# STM32F407_1.net
KiCad netlist of a schematic drawn in Altium Designer
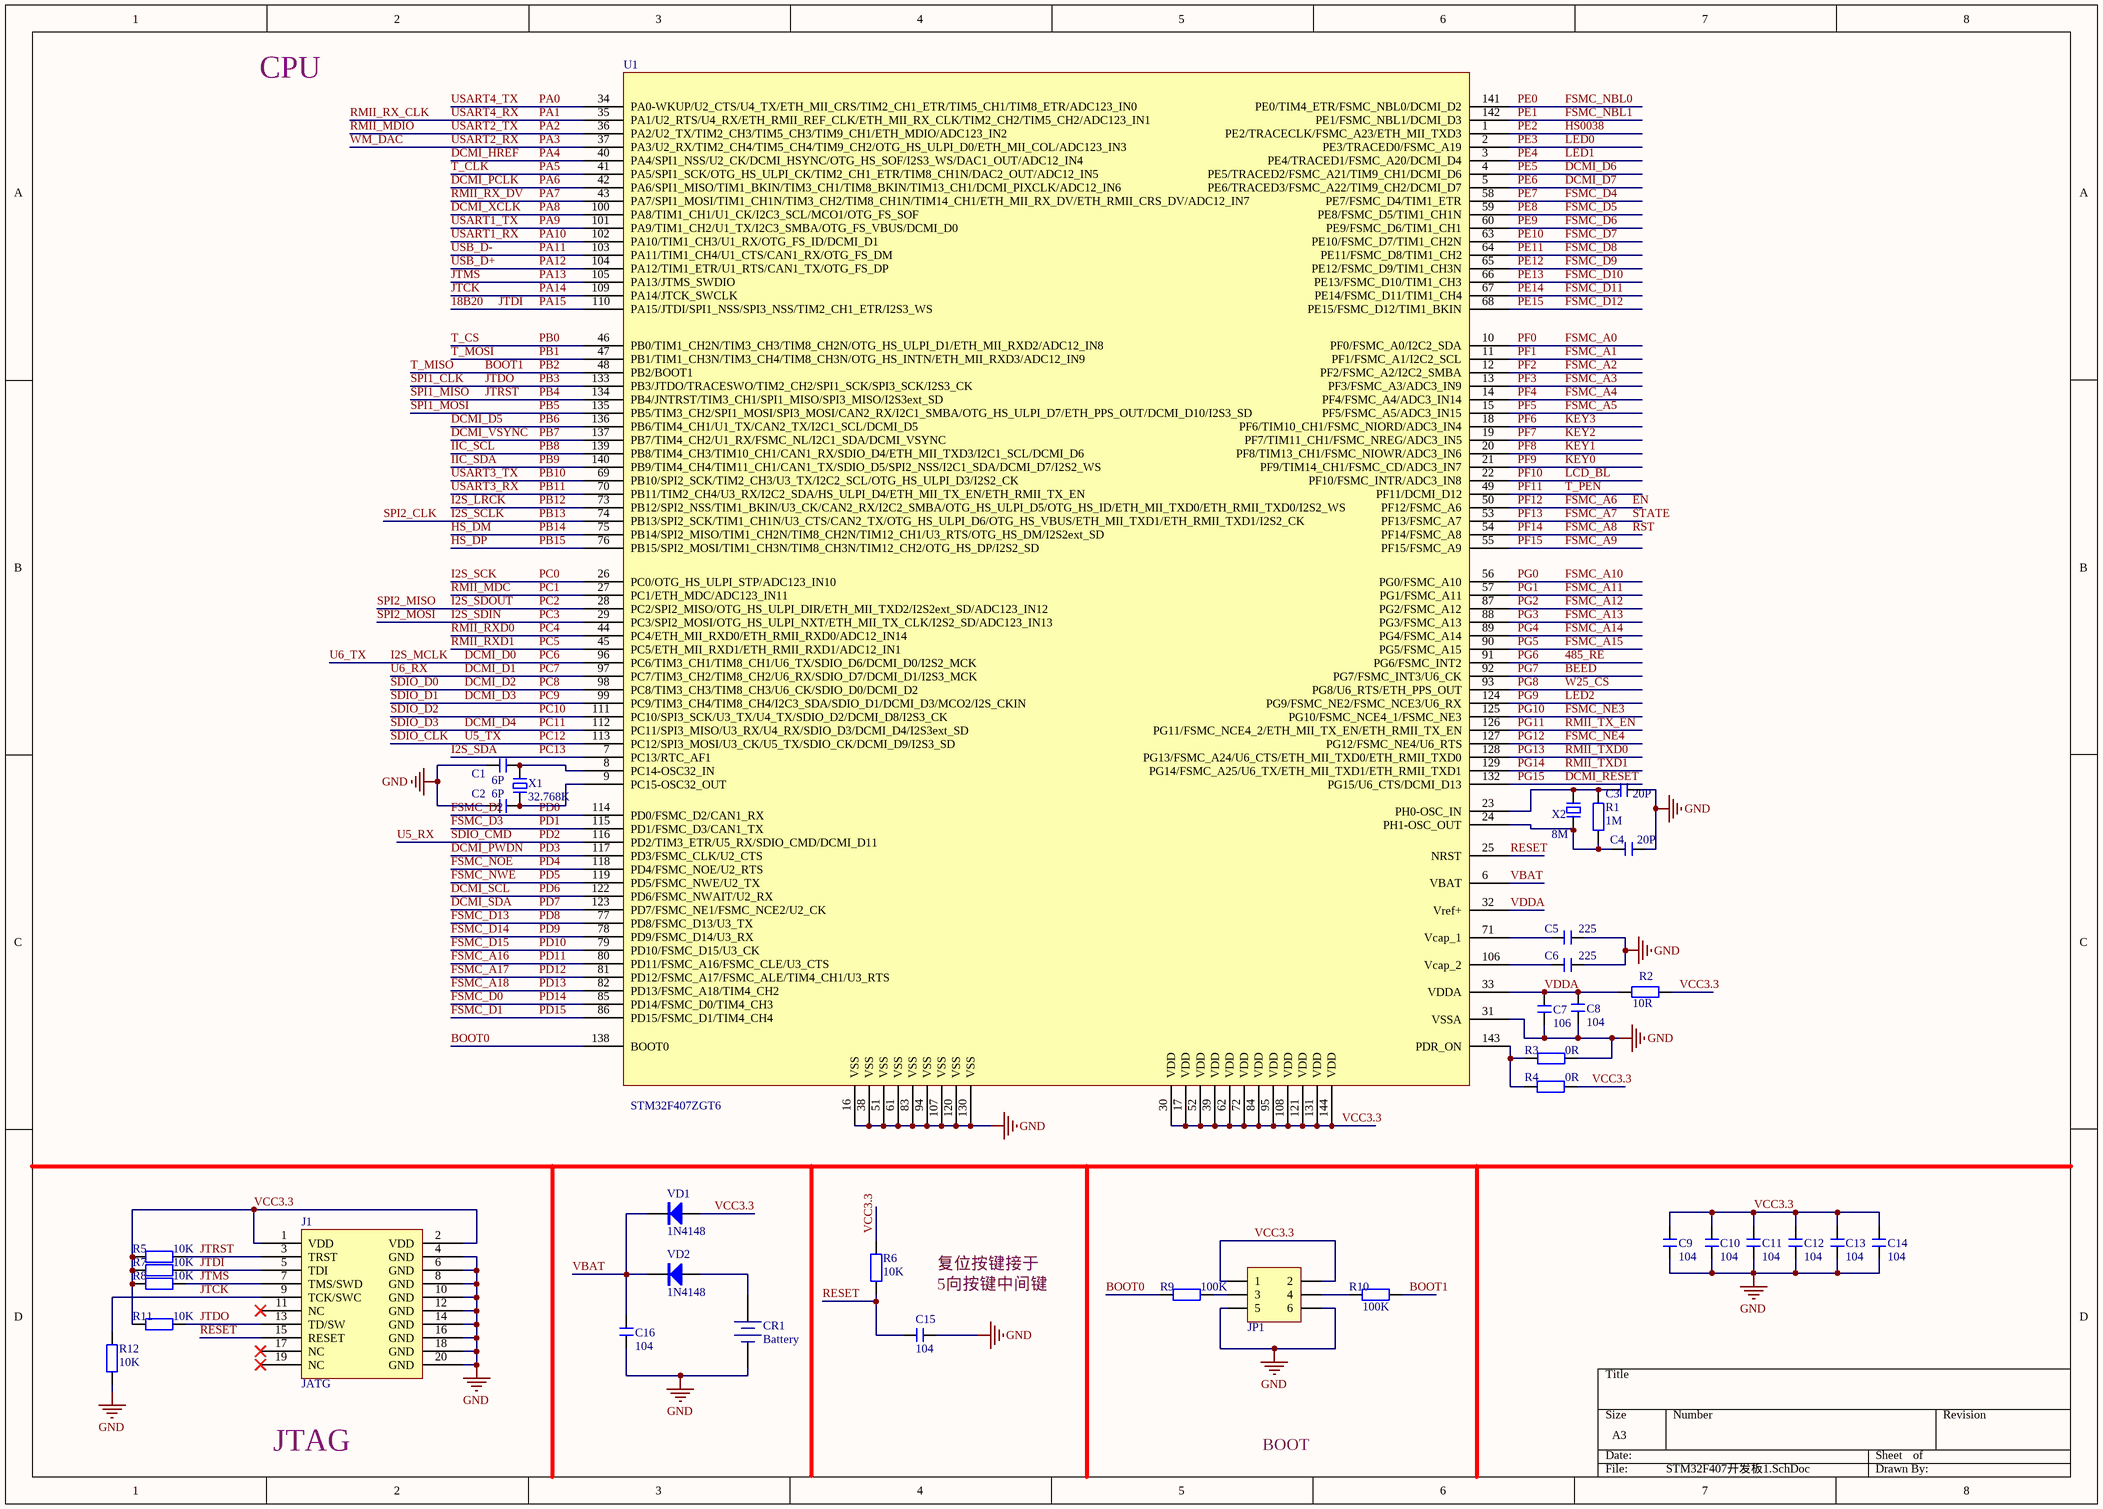
[diagram p0: STM32F407开发板1.SchDoc]

(export (version "E")
  (design (tool "Eeschema 10.0.6"))
  (components
    (comp (ref "C1")
      (value "6P")
      (footprint "C 0603")
      (description "无极性贴片电容")
      (fields (field (name "版权归属") "源创客"))
      (libsource (lib "电阻-电容-电感") (part "C"))
    )
    (comp (ref "C2")
      (value "6P")
      (footprint "C 0603")
      (description "无极性贴片电容")
      (fields (field (name "版权归属") "源创客"))
      (libsource (lib "电阻-电容-电感") (part "C"))
    )
    (comp (ref "C3")
      (value "20P")
      (footprint "C 0603")
      (description "无极性贴片电容")
      (fields (field (name "版权归属") "源创客"))
      (libsource (lib "电阻-电容-电感") (part "C"))
    )
    (comp (ref "C4")
      (value "20P")
      (footprint "C 0603")
      (description "无极性贴片电容")
      (fields (field (name "版权归属") "源创客"))
      (libsource (lib "电阻-电容-电感") (part "C"))
    )
    (comp (ref "C5")
      (value "225")
      (footprint "C 0603")
      (description "无极性贴片电容")
      (fields (field (name "版权归属") "源创客"))
      (libsource (lib "电阻-电容-电感") (part "C"))
    )
    (comp (ref "C6")
      (value "225")
      (footprint "C 0603")
      (description "无极性贴片电容")
      (fields (field (name "版权归属") "源创客"))
      (libsource (lib "电阻-电容-电感") (part "C"))
    )
    (comp (ref "C7")
      (value "106")
      (footprint "C 0603")
      (description "无极性贴片电容")
      (fields (field (name "版权归属") "源创客"))
      (libsource (lib "电阻-电容-电感") (part "C"))
    )
    (comp (ref "C8")
      (value "104")
      (footprint "C 0603")
      (description "无极性贴片电容")
      (fields (field (name "版权归属") "源创客"))
      (libsource (lib "电阻-电容-电感") (part "C"))
    )
    (comp (ref "C9")
      (value "104")
      (footprint "C 0603")
      (description "无极性贴片电容")
      (fields (field (name "版权归属") "源创客"))
      (libsource (lib "电阻-电容-电感") (part "C"))
    )
    (comp (ref "C10")
      (value "104")
      (footprint "C 0603")
      (description "无极性贴片电容")
      (fields (field (name "版权归属") "源创客"))
      (libsource (lib "电阻-电容-电感") (part "C"))
    )
    (comp (ref "C11")
      (value "104")
      (footprint "C 0603")
      (description "无极性贴片电容")
      (fields (field (name "版权归属") "源创客"))
      (libsource (lib "电阻-电容-电感") (part "C"))
    )
    (comp (ref "C12")
      (value "104")
      (footprint "C 0603")
      (description "无极性贴片电容")
      (fields (field (name "版权归属") "源创客"))
      (libsource (lib "电阻-电容-电感") (part "C"))
    )
    (comp (ref "C13")
      (value "104")
      (footprint "C 0603")
      (description "无极性贴片电容")
      (fields (field (name "版权归属") "源创客"))
      (libsource (lib "电阻-电容-电感") (part "C"))
    )
    (comp (ref "C14")
      (value "104")
      (footprint "C 0603")
      (description "无极性贴片电容")
      (fields (field (name "版权归属") "源创客"))
      (libsource (lib "电阻-电容-电感") (part "C"))
    )
    (comp (ref "C15")
      (value "104")
      (footprint "C 0603")
      (description "无极性贴片电容")
      (fields (field (name "版权归属") "源创客"))
      (libsource (lib "电阻-电容-电感") (part "C"))
    )
    (comp (ref "C16")
      (value "104")
      (footprint "C 0603")
      (description "无极性贴片电容")
      (fields (field (name "版权归属") "源创客"))
      (libsource (lib "电阻-电容-电感") (part "C"))
    )
    (comp (ref "CR1")
      (value "Battery")
      (footprint "CR1220_A")
      (description "微型电池")
      (fields (field (name "版权归属") "源创客"))
      (libsource (lib "未分类器件") (part "CR-3V"))
    )
    (comp (ref "J1") (value "JATG") (footprint "HDR-10X2") (libsource (lib "接口类") (part "JATG")))
    (comp (ref "JP1")
      (value "Header3X2")
      (footprint "HDR-3X2")
      (description "3*2P接插件")
      (fields (field (name "版权归属") "源创客"))
      (libsource (lib "接插件") (part "Header 3X2"))
    )
    (comp (ref "R1")
      (value "1M")
      (footprint "R 0603")
      (description "贴片电阻")
      (fields (field (name "版权归属") "源创客"))
      (libsource (lib "电阻-电容-电感") (part "R"))
    )
    (comp (ref "R2")
      (value "10R")
      (footprint "R 0603")
      (description "贴片电阻")
      (fields (field (name "版权归属") "源创客"))
      (libsource (lib "电阻-电容-电感") (part "R"))
    )
    (comp (ref "R3")
      (value "0R")
      (footprint "R 0603")
      (description "贴片电阻")
      (fields (field (name "版权归属") "源创客"))
      (libsource (lib "电阻-电容-电感") (part "R"))
    )
    (comp (ref "R4")
      (value "0R")
      (footprint "R 0603")
      (description "贴片电阻")
      (fields (field (name "版权归属") "源创客"))
      (libsource (lib "电阻-电容-电感") (part "R"))
    )
    (comp (ref "R5")
      (value "10K")
      (footprint "R 0603")
      (description "贴片电阻")
      (fields (field (name "版权归属") "源创客"))
      (libsource (lib "电阻-电容-电感") (part "R"))
    )
    (comp (ref "R6")
      (value "10K")
      (footprint "R 0603")
      (description "贴片电阻")
      (fields (field (name "版权归属") "源创客"))
      (libsource (lib "电阻-电容-电感") (part "R"))
    )
    (comp (ref "R7")
      (value "10K")
      (footprint "R 0603")
      (description "贴片电阻")
      (fields (field (name "版权归属") "源创客"))
      (libsource (lib "电阻-电容-电感") (part "R"))
    )
    (comp (ref "R8")
      (value "10K")
      (footprint "R 0603")
      (description "贴片电阻")
      (fields (field (name "版权归属") "源创客"))
      (libsource (lib "电阻-电容-电感") (part "R"))
    )
    (comp (ref "R9")
      (value "100K")
      (footprint "R 0603")
      (description "贴片电阻")
      (fields (field (name "版权归属") "源创客"))
      (libsource (lib "电阻-电容-电感") (part "R"))
    )
    (comp (ref "R10")
      (value "100K")
      (footprint "R 0603")
      (description "贴片电阻")
      (fields (field (name "版权归属") "源创客"))
      (libsource (lib "电阻-电容-电感") (part "R"))
    )
    (comp (ref "R11")
      (value "10K")
      (footprint "R 0603")
      (description "贴片电阻")
      (fields (field (name "版权归属") "源创客"))
      (libsource (lib "电阻-电容-电感") (part "R"))
    )
    (comp (ref "R12")
      (value "10K")
      (footprint "R 0603")
      (description "贴片电阻")
      (fields (field (name "版权归属") "源创客"))
      (libsource (lib "电阻-电容-电感") (part "R"))
    )
    (comp (ref "U1")
      (value "STM32F407ZGT6")
      (footprint "TQFP144 20x20_L")
      (libsource (lib "STM8系列单片机") (part "STM32F407ZGT6"))
    )
    (comp (ref "VD1")
      (value "1N4148")
      (footprint "MINI_MELF (LL34)")
      (description "高速开关二极管")
      (fields (field (name "版权归属") "源创客"))
      (libsource (lib "二极管-整流桥") (part "1N4148"))
    )
    (comp (ref "VD2")
      (value "1N4148")
      (footprint "MINI_MELF (LL34)")
      (description "高速开关二极管")
      (fields (field (name "版权归属") "源创客"))
      (libsource (lib "二极管-整流桥") (part "1N4148"))
    )
    (comp (ref "X1")
      (value "32.768K")
      (footprint "XTAL-4S8")
      (description "2脚晶振")
      (fields (field (name "版权归属") "源创客"))
      (libsource (lib "保险丝-晶振") (part "XTAL-2"))
    )
    (comp (ref "X2")
      (value "8M")
      (footprint "XTAL-49S SMD")
      (description "2脚晶振")
      (fields (field (name "版权归属") "源创客"))
      (libsource (lib "保险丝-晶振") (part "XTAL-2"))
    )
  )
  (nets
    (net (code "1") (name "/18B20") (class "Default")
      (node (ref "J1") (pin "5") (pinfunction "TDI_5") (pintype "passive"))
      (node (ref "R7") (pin "2") (pinfunction "2_2") (pintype "passive"))
      (node (ref "U1") (pin "110") (pinfunction "PA15/JTDI/SPI1_NSS/SPI3_NSS/TIM2_CH1_ETR/I2S3_WS_110") (pintype "passive"))
    )
    (net (code "2") (name "/485_RE") (class "Default")
      (node (ref "U1") (pin "91") (pinfunction "PG6/FSMC_INT2_91") (pintype "passive"))
    )
    (net (code "3") (name "/BEED") (class "Default")
      (node (ref "U1") (pin "92") (pinfunction "PG7/FSMC_INT3/U6_CK_92") (pintype "passive"))
    )
    (net (code "4") (name "/BOOT0") (class "Default")
      (node (ref "R9") (pin "1") (pinfunction "1_1") (pintype "passive"))
      (node (ref "U1") (pin "138") (pinfunction "BOOT0_138") (pintype "passive"))
    )
    (net (code "5") (name "/BOOT1") (class "Default")
      (node (ref "R10") (pin "2") (pinfunction "2_2") (pintype "passive"))
      (node (ref "U1") (pin "48") (pinfunction "PB2/BOOT1_48") (pintype "passive"))
    )
    (net (code "6") (name "/DCMI_D0") (class "Default")
      (node (ref "U1") (pin "96") (pinfunction "PC6/TIM3_CH1/TIM8_CH1/U6_TX/SDIO_D6/DCMI_D0/I2S2_MCK_96") (pintype "passive"))
    )
    (net (code "7") (name "/DCMI_D1") (class "Default")
      (node (ref "U1") (pin "97") (pinfunction "PC7/TIM3_CH2/TIM8_CH2/U6_RX/SDIO_D7/DCMI_D1/I2S3_MCK_97") (pintype "passive"))
    )
    (net (code "8") (name "/DCMI_D2") (class "Default")
      (node (ref "U1") (pin "98") (pinfunction "PC8/TIM3_CH3/TIM8_CH3/U6_CK/SDIO_D0/DCMI_D2_98") (pintype "passive"))
    )
    (net (code "9") (name "/DCMI_D3") (class "Default")
      (node (ref "U1") (pin "99") (pinfunction "PC9/TIM3_CH4/TIM8_CH4/I2C3_SDA/SDIO_D1/DCMI_D3/MCO2/I2S_CKIN_99") (pintype "passive"))
    )
    (net (code "10") (name "/DCMI_D4") (class "Default")
      (node (ref "U1") (pin "112") (pinfunction "PC11/SPI3_MISO/U3_RX/U4_RX/SDIO_D3/DCMI_D4/I2S3ext_SD_112") (pintype "passive"))
    )
    (net (code "11") (name "/DCMI_D5") (class "Default")
      (node (ref "U1") (pin "136") (pinfunction "PB6/TIM4_CH1/U1_TX/CAN2_TX/I2C1_SCL/DCMI_D5_136") (pintype "passive"))
    )
    (net (code "12") (name "/DCMI_D6") (class "Default")
      (node (ref "U1") (pin "4") (pinfunction "PE5/TRACED2/FSMC_A21/TIM9_CH1/DCMI_D6_4") (pintype "passive"))
    )
    (net (code "13") (name "/DCMI_D7") (class "Default")
      (node (ref "U1") (pin "5") (pinfunction "PE6/TRACED3/FSMC_A22/TIM9_CH2/DCMI_D7_5") (pintype "passive"))
    )
    (net (code "14") (name "/DCMI_HREF") (class "Default")
      (node (ref "U1") (pin "40") (pinfunction "PA4/SPI1_NSS/U2_CK/DCMI_HSYNC/OTG_HS_SOF/I2S3_WS/DAC1_OUT/ADC12_IN4_40") (pintype "passive"))
    )
    (net (code "15") (name "/DCMI_PCLK") (class "Default")
      (node (ref "U1") (pin "42") (pinfunction "PA6/SPI1_MISO/TIM1_BKIN/TIM3_CH1/TIM8_BKIN/TIM13_CH1/DCMI_PIXCLK/ADC12_IN6_42") (pintype "passive"))
    )
    (net (code "16") (name "/DCMI_PWDN") (class "Default")
      (node (ref "U1") (pin "117") (pinfunction "PD3/FSMC_CLK/U2_CTS_117") (pintype "passive"))
    )
    (net (code "17") (name "/DCMI_RESET") (class "Default")
      (node (ref "U1") (pin "132") (pinfunction "PG15/U6_CTS/DCMI_D13_132") (pintype "passive"))
    )
    (net (code "18") (name "/DCMI_SCL") (class "Default")
      (node (ref "U1") (pin "122") (pinfunction "PD6/FSMC_NWAIT/U2_RX_122") (pintype "passive"))
    )
    (net (code "19") (name "/DCMI_SDA") (class "Default")
      (node (ref "U1") (pin "123") (pinfunction "PD7/FSMC_NE1/FSMC_NCE2/U2_CK_123") (pintype "passive"))
    )
    (net (code "20") (name "/DCMI_VSYNC") (class "Default")
      (node (ref "U1") (pin "137") (pinfunction "PB7/TIM4_CH2/U1_RX/FSMC_NL/I2C1_SDA/DCMI_VSYNC_137") (pintype "passive"))
    )
    (net (code "21") (name "/DCMI_XCLK") (class "Default")
      (node (ref "U1") (pin "100") (pinfunction "PA8/TIM1_CH1/U1_CK/I2C3_SCL/MCO1/OTG_FS_SOF_100") (pintype "passive"))
    )
    (net (code "22") (name "/EN") (class "Default")
      (node (ref "U1") (pin "50") (pinfunction "PF12/FSMC_A6_50") (pintype "passive"))
    )
    (net (code "23") (name "/FSMC_A0") (class "Default")
      (node (ref "U1") (pin "10") (pinfunction "PF0/FSMC_A0/I2C2_SDA_10") (pintype "passive"))
    )
    (net (code "24") (name "/FSMC_A1") (class "Default")
      (node (ref "U1") (pin "11") (pinfunction "PF1/FSMC_A1/I2C2_SCL_11") (pintype "passive"))
    )
    (net (code "25") (name "/FSMC_A2") (class "Default")
      (node (ref "U1") (pin "12") (pinfunction "PF2/FSMC_A2/I2C2_SMBA_12") (pintype "passive"))
    )
    (net (code "26") (name "/FSMC_A3") (class "Default")
      (node (ref "U1") (pin "13") (pinfunction "PF3/FSMC_A3/ADC3_IN9_13") (pintype "passive"))
    )
    (net (code "27") (name "/FSMC_A4") (class "Default")
      (node (ref "U1") (pin "14") (pinfunction "PF4/FSMC_A4/ADC3_IN14_14") (pintype "passive"))
    )
    (net (code "28") (name "/FSMC_A5") (class "Default")
      (node (ref "U1") (pin "15") (pinfunction "PF5/FSMC_A5/ADC3_IN15_15") (pintype "passive"))
    )
    (net (code "29") (name "/FSMC_A7") (class "Default")
      (node (ref "U1") (pin "53") (pinfunction "PF13/FSMC_A7_53") (pintype "passive"))
    )
    (net (code "30") (name "/FSMC_A8") (class "Default")
      (node (ref "U1") (pin "54") (pinfunction "PF14/FSMC_A8_54") (pintype "passive"))
    )
    (net (code "31") (name "/FSMC_A9") (class "Default")
      (node (ref "U1") (pin "55") (pinfunction "PF15/FSMC_A9_55") (pintype "passive"))
    )
    (net (code "32") (name "/FSMC_A10") (class "Default")
      (node (ref "U1") (pin "56") (pinfunction "PG0/FSMC_A10_56") (pintype "passive"))
    )
    (net (code "33") (name "/FSMC_A11") (class "Default")
      (node (ref "U1") (pin "57") (pinfunction "PG1/FSMC_A11_57") (pintype "passive"))
    )
    (net (code "34") (name "/FSMC_A12") (class "Default")
      (node (ref "U1") (pin "87") (pinfunction "PG2/FSMC_A12_87") (pintype "passive"))
    )
    (net (code "35") (name "/FSMC_A13") (class "Default")
      (node (ref "U1") (pin "88") (pinfunction "PG3/FSMC_A13_88") (pintype "passive"))
    )
    (net (code "36") (name "/FSMC_A14") (class "Default")
      (node (ref "U1") (pin "89") (pinfunction "PG4/FSMC_A14_89") (pintype "passive"))
    )
    (net (code "37") (name "/FSMC_A15") (class "Default")
      (node (ref "U1") (pin "90") (pinfunction "PG5/FSMC_A15_90") (pintype "passive"))
    )
    (net (code "38") (name "/FSMC_A16") (class "Default")
      (node (ref "U1") (pin "80") (pinfunction "PD11/FSMC_A16/FSMC_CLE/U3_CTS_80") (pintype "passive"))
    )
    (net (code "39") (name "/FSMC_A17") (class "Default")
      (node (ref "U1") (pin "81") (pinfunction "PD12/FSMC_A17/FSMC_ALE/TIM4_CH1/U3_RTS_81") (pintype "passive"))
    )
    (net (code "40") (name "/FSMC_A18") (class "Default")
      (node (ref "U1") (pin "82") (pinfunction "PD13/FSMC_A18/TIM4_CH2_82") (pintype "passive"))
    )
    (net (code "41") (name "/FSMC_D0") (class "Default")
      (node (ref "U1") (pin "85") (pinfunction "PD14/FSMC_D0/TIM4_CH3_85") (pintype "passive"))
    )
    (net (code "42") (name "/FSMC_D1") (class "Default")
      (node (ref "U1") (pin "86") (pinfunction "PD15/FSMC_D1/TIM4_CH4_86") (pintype "passive"))
    )
    (net (code "43") (name "/FSMC_D2") (class "Default")
      (node (ref "U1") (pin "114") (pinfunction "PD0/FSMC_D2/CAN1_RX_114") (pintype "passive"))
    )
    (net (code "44") (name "/FSMC_D3") (class "Default")
      (node (ref "U1") (pin "115") (pinfunction "PD1/FSMC_D3/CAN1_TX_115") (pintype "passive"))
    )
    (net (code "45") (name "/FSMC_D4") (class "Default")
      (node (ref "U1") (pin "58") (pinfunction "PE7/FSMC_D4/TIM1_ETR_58") (pintype "passive"))
    )
    (net (code "46") (name "/FSMC_D5") (class "Default")
      (node (ref "U1") (pin "59") (pinfunction "PE8/FSMC_D5/TIM1_CH1N_59") (pintype "passive"))
    )
    (net (code "47") (name "/FSMC_D6") (class "Default")
      (node (ref "U1") (pin "60") (pinfunction "PE9/FSMC_D6/TIM1_CH1_60") (pintype "passive"))
    )
    (net (code "48") (name "/FSMC_D7") (class "Default")
      (node (ref "U1") (pin "63") (pinfunction "PE10/FSMC_D7/TIM1_CH2N_63") (pintype "passive"))
    )
    (net (code "49") (name "/FSMC_D8") (class "Default")
      (node (ref "U1") (pin "64") (pinfunction "PE11/FSMC_D8/TIM1_CH2_64") (pintype "passive"))
    )
    (net (code "50") (name "/FSMC_D9") (class "Default")
      (node (ref "U1") (pin "65") (pinfunction "PE12/FSMC_D9/TIM1_CH3N_65") (pintype "passive"))
    )
    (net (code "51") (name "/FSMC_D10") (class "Default")
      (node (ref "U1") (pin "66") (pinfunction "PE13/FSMC_D10/TIM1_CH3_66") (pintype "passive"))
    )
    (net (code "52") (name "/FSMC_D11") (class "Default")
      (node (ref "U1") (pin "67") (pinfunction "PE14/FSMC_D11/TIM1_CH4_67") (pintype "passive"))
    )
    (net (code "53") (name "/FSMC_D12") (class "Default")
      (node (ref "U1") (pin "68") (pinfunction "PE15/FSMC_D12/TIM1_BKIN_68") (pintype "passive"))
    )
    (net (code "54") (name "/FSMC_D13") (class "Default")
      (node (ref "U1") (pin "77") (pinfunction "PD8/FSMC_D13/U3_TX_77") (pintype "passive"))
    )
    (net (code "55") (name "/FSMC_D14") (class "Default")
      (node (ref "U1") (pin "78") (pinfunction "PD9/FSMC_D14/U3_RX_78") (pintype "passive"))
    )
    (net (code "56") (name "/FSMC_D15") (class "Default")
      (node (ref "U1") (pin "79") (pinfunction "PD10/FSMC_D15/U3_CK_79") (pintype "passive"))
    )
    (net (code "57") (name "/FSMC_NBL0") (class "Default")
      (node (ref "U1") (pin "141") (pinfunction "PE0/TIM4_ETR/FSMC_NBL0/DCMI_D2_141") (pintype "passive"))
    )
    (net (code "58") (name "/FSMC_NBL1") (class "Default")
      (node (ref "U1") (pin "142") (pinfunction "PE1/FSMC_NBL1/DCMI_D3_142") (pintype "passive"))
    )
    (net (code "59") (name "/FSMC_NE3") (class "Default")
      (node (ref "U1") (pin "125") (pinfunction "PG10/FSMC_NCE4_1/FSMC_NE3_125") (pintype "passive"))
    )
    (net (code "60") (name "/FSMC_NE4") (class "Default")
      (node (ref "U1") (pin "127") (pinfunction "PG12/FSMC_NE4/U6_RTS_127") (pintype "passive"))
    )
    (net (code "61") (name "/FSMC_NOE") (class "Default")
      (node (ref "U1") (pin "118") (pinfunction "PD4/FSMC_NOE/U2_RTS_118") (pintype "passive"))
    )
    (net (code "62") (name "/FSMC_NWE") (class "Default")
      (node (ref "U1") (pin "119") (pinfunction "PD5/FSMC_NWE/U2_TX_119") (pintype "passive"))
    )
    (net (code "63") (name "/HS0038") (class "Default")
      (node (ref "U1") (pin "1") (pinfunction "PE2/TRACECLK/FSMC_A23/ETH_MII_TXD3_1") (pintype "passive"))
    )
    (net (code "64") (name "/HS_DM") (class "Default")
      (node (ref "U1") (pin "75") (pinfunction "PB14/SPI2_MISO/TIM1_CH2N/TIM8_CH2N/TIM12_CH1/U3_RTS/OTG_HS_DM/I2S2ext_SD_75") (pintype "passive"))
    )
    (net (code "65") (name "/HS_DP") (class "Default")
      (node (ref "U1") (pin "76") (pinfunction "PB15/SPI2_MOSI/TIM1_CH3N/TIM8_CH3N/TIM12_CH2/OTG_HS_DP/I2S2_SD_76") (pintype "passive"))
    )
    (net (code "66") (name "/I2S_LRCK") (class "Default")
      (node (ref "U1") (pin "73") (pinfunction "PB12/SPI2_NSS/TIM1_BKIN/U3_CK/CAN2_RX/I2C2_SMBA/OTG_HS_ULPI_D5/OTG_HS_ID/ETH_MII_TXD0/ETH_RMII_TXD0/I2S2_WS_73") (pintype "passive"))
    )
    (net (code "67") (name "/I2S_SCK") (class "Default")
      (node (ref "U1") (pin "26") (pinfunction "PC0/OTG_HS_ULPI_STP/ADC123_IN10_26") (pintype "passive"))
    )
    (net (code "68") (name "/I2S_SCLK") (class "Default")
      (node (ref "U1") (pin "74") (pinfunction "PB13/SPI2_SCK/TIM1_CH1N/U3_CTS/CAN2_TX/OTG_HS_ULPI_D6/OTG_HS_VBUS/ETH_MII_TXD1/ETH_RMII_TXD1/I2S2_CK_74") (pintype "passive"))
    )
    (net (code "69") (name "/I2S_SDA") (class "Default")
      (node (ref "U1") (pin "7") (pinfunction "PC13/RTC_AF1_7") (pintype "passive"))
    )
    (net (code "70") (name "/I2S_SDIN") (class "Default")
      (node (ref "U1") (pin "29") (pinfunction "PC3/SPI2_MOSI/OTG_HS_ULPI_NXT/ETH_MII_TX_CLK/I2S2_SD/ADC123_IN13_29") (pintype "passive"))
    )
    (net (code "71") (name "/I2S_SDOUT") (class "Default")
      (node (ref "U1") (pin "28") (pinfunction "PC2/SPI2_MISO/OTG_HS_ULPI_DIR/ETH_MII_TXD2/I2S2ext_SD/ADC123_IN12_28") (pintype "passive"))
    )
    (net (code "72") (name "/IIC_SCL") (class "Default")
      (node (ref "U1") (pin "139") (pinfunction "PB8/TIM4_CH3/TIM10_CH1/CAN1_RX/SDIO_D4/ETH_MII_TXD3/I2C1_SCL/DCMI_D6_139") (pintype "passive"))
    )
    (net (code "73") (name "/IIC_SDA") (class "Default")
      (node (ref "U1") (pin "140") (pinfunction "PB9/TIM4_CH4/TIM11_CH1/CAN1_TX/SDIO_D5/SPI2_NSS/I2C1_SDA/DCMI_D7/I2S2_WS_140") (pintype "passive"))
    )
    (net (code "74") (name "/JTCK") (class "Default")
      (node (ref "J1") (pin "9") (pinfunction "TCK/SWC_9") (pintype "passive"))
      (node (ref "R12") (pin "2") (pinfunction "2_2") (pintype "passive"))
      (node (ref "U1") (pin "109") (pinfunction "PA14/JTCK_SWCLK_109") (pintype "passive"))
    )
    (net (code "75") (name "/JTDO") (class "Default")
      (node (ref "J1") (pin "13") (pinfunction "TD/SW_13") (pintype "passive"))
      (node (ref "R11") (pin "2") (pinfunction "2_2") (pintype "passive"))
      (node (ref "U1") (pin "133") (pinfunction "PB3/JTDO/TRACESWO/TIM2_CH2/SPI1_SCK/SPI3_SCK/I2S3_CK_133") (pintype "passive"))
    )
    (net (code "76") (name "/JTMS") (class "Default")
      (node (ref "J1") (pin "7") (pinfunction "TMS/SWD_7") (pintype "passive"))
      (node (ref "R8") (pin "2") (pinfunction "2_2") (pintype "passive"))
      (node (ref "U1") (pin "105") (pinfunction "PA13/JTMS_SWDIO_105") (pintype "passive"))
    )
    (net (code "77") (name "/JTRST") (class "Default")
      (node (ref "J1") (pin "3") (pinfunction "TRST_3") (pintype "passive"))
      (node (ref "R5") (pin "2") (pinfunction "2_2") (pintype "passive"))
      (node (ref "U1") (pin "134") (pinfunction "PB4/JNTRST/TIM3_CH1/SPI1_MISO/SPI3_MISO/I2S3ext_SD_134") (pintype "passive"))
    )
    (net (code "78") (name "/KEY0") (class "Default")
      (node (ref "U1") (pin "21") (pinfunction "PF9/TIM14_CH1/FSMC_CD/ADC3_IN7_21") (pintype "passive"))
    )
    (net (code "79") (name "/KEY1") (class "Default")
      (node (ref "U1") (pin "20") (pinfunction "PF8/TIM13_CH1/FSMC_NIOWR/ADC3_IN6_20") (pintype "passive"))
    )
    (net (code "80") (name "/KEY2") (class "Default")
      (node (ref "U1") (pin "19") (pinfunction "PF7/TIM11_CH1/FSMC_NREG/ADC3_IN5_19") (pintype "passive"))
    )
    (net (code "81") (name "/KEY3") (class "Default")
      (node (ref "U1") (pin "18") (pinfunction "PF6/TIM10_CH1/FSMC_NIORD/ADC3_IN4_18") (pintype "passive"))
    )
    (net (code "82") (name "/LCD_BL") (class "Default")
      (node (ref "U1") (pin "22") (pinfunction "PF10/FSMC_INTR/ADC3_IN8_22") (pintype "passive"))
    )
    (net (code "83") (name "/LED0") (class "Default")
      (node (ref "U1") (pin "2") (pinfunction "PE3/TRACED0/FSMC_A19_2") (pintype "passive"))
    )
    (net (code "84") (name "/LED1") (class "Default")
      (node (ref "U1") (pin "3") (pinfunction "PE4/TRACED1/FSMC_A20/DCMI_D4_3") (pintype "passive"))
    )
    (net (code "85") (name "/LED2") (class "Default")
      (node (ref "U1") (pin "124") (pinfunction "PG9/FSMC_NE2/FSMC_NCE3/U6_RX_124") (pintype "passive"))
    )
    (net (code "86") (name "/PA0") (class "Default")
      (node (ref "U1") (pin "34") (pinfunction "PA0-WKUP/U2_CTS/U4_TX/ETH_MII_CRS/TIM2_CH1_ETR/TIM5_CH1/TIM8_ETR/ADC123_IN0_34") (pintype "passive"))
    )
    (net (code "87") (name "/PA1") (class "Default")
      (node (ref "U1") (pin "35") (pinfunction "PA1/U2_RTS/U4_RX/ETH_RMII_REF_CLK/ETH_MII_RX_CLK/TIM2_CH2/TIM5_CH2/ADC123_IN1_35") (pintype "passive"))
    )
    (net (code "88") (name "/PA2") (class "Default")
      (node (ref "U1") (pin "36") (pinfunction "PA2/U2_TX/TIM2_CH3/TIM5_CH3/TIM9_CH1/ETH_MDIO/ADC123_IN2_36") (pintype "passive"))
    )
    (net (code "89") (name "/PA3") (class "Default")
      (node (ref "U1") (pin "37") (pinfunction "PA3/U2_RX/TIM2_CH4/TIM5_CH4/TIM9_CH2/OTG_HS_ULPI_D0/ETH_MII_COL/ADC123_IN3_37") (pintype "passive"))
    )
    (net (code "90") (name "/PA5") (class "Default")
      (node (ref "U1") (pin "41") (pinfunction "PA5/SPI1_SCK/OTG_HS_ULPI_CK/TIM2_CH1_ETR/TIM8_CH1N/DAC2_OUT/ADC12_IN5_41") (pintype "passive"))
    )
    (net (code "91") (name "/PA7") (class "Default")
      (node (ref "U1") (pin "43") (pinfunction "PA7/SPI1_MOSI/TIM1_CH1N/TIM3_CH2/TIM8_CH1N/TIM14_CH1/ETH_MII_RX_DV/ETH_RMII_CRS_DV/ADC12_IN7_43") (pintype "passive"))
    )
    (net (code "92") (name "/PA9") (class "Default")
      (node (ref "U1") (pin "101") (pinfunction "PA9/TIM1_CH2/U1_TX/I2C3_SMBA/OTG_FS_VBUS/DCMI_D0_101") (pintype "passive"))
    )
    (net (code "93") (name "/PA10") (class "Default")
      (node (ref "U1") (pin "102") (pinfunction "PA10/TIM1_CH3/U1_RX/OTG_FS_ID/DCMI_D1_102") (pintype "passive"))
    )
    (net (code "94") (name "/PA11") (class "Default")
      (node (ref "U1") (pin "103") (pinfunction "PA11/TIM1_CH4/U1_CTS/CAN1_RX/OTG_FS_DM_103") (pintype "passive"))
    )
    (net (code "95") (name "/PA12") (class "Default")
      (node (ref "U1") (pin "104") (pinfunction "PA12/TIM1_ETR/U1_RTS/CAN1_TX/OTG_FS_DP_104") (pintype "passive"))
    )
    (net (code "96") (name "/PB0") (class "Default")
      (node (ref "U1") (pin "46") (pinfunction "PB0/TIM1_CH2N/TIM3_CH3/TIM8_CH2N/OTG_HS_ULPI_D1/ETH_MII_RXD2/ADC12_IN8_46") (pintype "passive"))
    )
    (net (code "97") (name "/PB1") (class "Default")
      (node (ref "U1") (pin "47") (pinfunction "PB1/TIM1_CH3N/TIM3_CH4/TIM8_CH3N/OTG_HS_INTN/ETH_MII_RXD3/ADC12_IN9_47") (pintype "passive"))
    )
    (net (code "98") (name "/PB5") (class "Default")
      (node (ref "U1") (pin "135") (pinfunction "PB5/TIM3_CH2/SPI1_MOSI/SPI3_MOSI/CAN2_RX/I2C1_SMBA/OTG_HS_ULPI_D7/ETH_PPS_OUT/DCMI_D10/I2S3_SD_135") (pintype "passive"))
    )
    (net (code "99") (name "/PB10") (class "Default")
      (node (ref "U1") (pin "69") (pinfunction "PB10/SPI2_SCK/TIM2_CH3/U3_TX/I2C2_SCL/OTG_HS_ULPI_D3/I2S2_CK_69") (pintype "passive"))
    )
    (net (code "100") (name "/PB11") (class "Default")
      (node (ref "U1") (pin "70") (pinfunction "PB11/TIM2_CH4/U3_RX/I2C2_SDA/HS_ULPI_D4/ETH_MII_TX_EN/ETH_RMII_TX_EN_70") (pintype "passive"))
    )
    (net (code "101") (name "/PC1") (class "Default")
      (node (ref "U1") (pin "27") (pinfunction "PC1/ETH_MDC/ADC123_IN11_27") (pintype "passive"))
    )
    (net (code "102") (name "/PC4") (class "Default")
      (node (ref "U1") (pin "44") (pinfunction "PC4/ETH_MII_RXD0/ETH_RMII_RXD0/ADC12_IN14_44") (pintype "passive"))
    )
    (net (code "103") (name "/PC5") (class "Default")
      (node (ref "U1") (pin "45") (pinfunction "PC5/ETH_MII_RXD1/ETH_RMII_RXD1/ADC12_IN1_45") (pintype "passive"))
    )
    (net (code "104") (name "/PC10") (class "Default")
      (node (ref "U1") (pin "111") (pinfunction "PC10/SPI3_SCK/U3_TX/U4_TX/SDIO_D2/DCMI_D8/I2S3_CK_111") (pintype "passive"))
    )
    (net (code "105") (name "/PC12") (class "Default")
      (node (ref "U1") (pin "113") (pinfunction "PC12/SPI3_MOSI/U3_CK/U5_TX/SDIO_CK/DCMI_D9/I2S3_SD_113") (pintype "passive"))
    )
    (net (code "106") (name "/PD2") (class "Default")
      (node (ref "U1") (pin "116") (pinfunction "PD2/TIM3_ETR/U5_RX/SDIO_CMD/DCMI_D11_116") (pintype "passive"))
    )
    (net (code "107") (name "/PF11") (class "Default")
      (node (ref "U1") (pin "49") (pinfunction "PF11/DCMI_D12_49") (pintype "passive"))
    )
    (net (code "108") (name "/PG8") (class "Default")
      (node (ref "U1") (pin "93") (pinfunction "PG8/U6_RTS/ETH_PPS_OUT_93") (pintype "passive"))
    )
    (net (code "109") (name "/PG11") (class "Default")
      (node (ref "U1") (pin "126") (pinfunction "PG11/FSMC_NCE4_2/ETH_MII_TX_EN/ETH_RMII_TX_EN_126") (pintype "passive"))
    )
    (net (code "110") (name "/PG13") (class "Default")
      (node (ref "U1") (pin "128") (pinfunction "PG13/FSMC_A24/U6_CTS/ETH_MII_TXD0/ETH_RMII_TXD0_128") (pintype "passive"))
    )
    (net (code "111") (name "/PG14") (class "Default")
      (node (ref "U1") (pin "129") (pinfunction "PG14/FSMC_A25/U6_TX/ETH_MII_TXD1/ETH_RMII_TXD1_129") (pintype "passive"))
    )
    (net (code "112") (name "/RESET") (class "Default")
      (node (ref "C15") (pin "2") (pinfunction "2_2") (pintype "passive"))
      (node (ref "J1") (pin "15") (pinfunction "RESET_15") (pintype "passive"))
      (node (ref "R6") (pin "1") (pinfunction "1_1") (pintype "passive"))
      (node (ref "U1") (pin "25") (pinfunction "NRST_25") (pintype "passive"))
    )
    (net (code "113") (name "/VBAT") (class "Default")
      (node (ref "C16") (pin "2") (pinfunction "2_2") (pintype "passive"))
      (node (ref "U1") (pin "6") (pinfunction "VBAT_6") (pintype "passive"))
      (node (ref "VD1") (pin "2") (pinfunction "K_2") (pintype "passive"))
      (node (ref "VD2") (pin "2") (pinfunction "K_2") (pintype "passive"))
    )
    (net (code "114") (name "/VCC3.3") (class "Default")
      (node (ref "C10") (pin "2") (pinfunction "2_2") (pintype "passive"))
      (node (ref "C11") (pin "2") (pinfunction "2_2") (pintype "passive"))
      (node (ref "C12") (pin "2") (pinfunction "2_2") (pintype "passive"))
      (node (ref "C13") (pin "2") (pinfunction "2_2") (pintype "passive"))
      (node (ref "C14") (pin "2") (pinfunction "2_2") (pintype "passive"))
      (node (ref "C9") (pin "2") (pinfunction "2_2") (pintype "passive"))
      (node (ref "J1") (pin "1") (pinfunction "VDD_1") (pintype "passive"))
      (node (ref "J1") (pin "2") (pinfunction "VDD_2") (pintype "passive"))
      (node (ref "JP1") (pin "1") (pinfunction "1_1") (pintype "passive"))
      (node (ref "JP1") (pin "2") (pinfunction "2_2") (pintype "passive"))
      (node (ref "R11") (pin "1") (pinfunction "1_1") (pintype "passive"))
      (node (ref "R2") (pin "2") (pinfunction "2_2") (pintype "passive"))
      (node (ref "R4") (pin "2") (pinfunction "2_2") (pintype "passive"))
      (node (ref "R5") (pin "1") (pinfunction "1_1") (pintype "passive"))
      (node (ref "R6") (pin "2") (pinfunction "2_2") (pintype "passive"))
      (node (ref "R7") (pin "1") (pinfunction "1_1") (pintype "passive"))
      (node (ref "R8") (pin "1") (pinfunction "1_1") (pintype "passive"))
      (node (ref "U1") (pin "108") (pinfunction "VDD_108") (pintype "passive"))
      (node (ref "U1") (pin "121") (pinfunction "VDD_121") (pintype "passive"))
      (node (ref "U1") (pin "131") (pinfunction "VDD_131") (pintype "passive"))
      (node (ref "U1") (pin "144") (pinfunction "VDD_144") (pintype "passive"))
      (node (ref "U1") (pin "17") (pinfunction "VDD_17") (pintype "passive"))
      (node (ref "U1") (pin "30") (pinfunction "VDD_30") (pintype "passive"))
      (node (ref "U1") (pin "39") (pinfunction "VDD_39") (pintype "passive"))
      (node (ref "U1") (pin "52") (pinfunction "VDD_52") (pintype "passive"))
      (node (ref "U1") (pin "62") (pinfunction "VDD_62") (pintype "passive"))
      (node (ref "U1") (pin "72") (pinfunction "VDD_72") (pintype "passive"))
      (node (ref "U1") (pin "84") (pinfunction "VDD_84") (pintype "passive"))
      (node (ref "U1") (pin "95") (pinfunction "VDD_95") (pintype "passive"))
      (node (ref "VD1") (pin "1") (pinfunction "A_1") (pintype "passive"))
    )
    (net (code "115") (name "/VDDA") (class "Default")
      (node (ref "C7") (pin "2") (pinfunction "2_2") (pintype "passive"))
      (node (ref "C8") (pin "2") (pinfunction "2_2") (pintype "passive"))
      (node (ref "R2") (pin "1") (pinfunction "1_1") (pintype "passive"))
      (node (ref "U1") (pin "32") (pinfunction "Vref+_32") (pintype "passive"))
      (node (ref "U1") (pin "33") (pinfunction "VDDA_33") (pintype "passive"))
    )
    (net (code "116") (name "GND") (class "Default")
      (node (ref "C1") (pin "1") (pinfunction "1_1") (pintype "passive"))
      (node (ref "C10") (pin "1") (pinfunction "1_1") (pintype "passive"))
      (node (ref "C11") (pin "1") (pinfunction "1_1") (pintype "passive"))
      (node (ref "C12") (pin "1") (pinfunction "1_1") (pintype "passive"))
      (node (ref "C13") (pin "1") (pinfunction "1_1") (pintype "passive"))
      (node (ref "C14") (pin "1") (pinfunction "1_1") (pintype "passive"))
      (node (ref "C15") (pin "1") (pinfunction "1_1") (pintype "passive"))
      (node (ref "C16") (pin "1") (pinfunction "1_1") (pintype "passive"))
      (node (ref "C2") (pin "1") (pinfunction "1_1") (pintype "passive"))
      (node (ref "C3") (pin "1") (pinfunction "1_1") (pintype "passive"))
      (node (ref "C4") (pin "1") (pinfunction "1_1") (pintype "passive"))
      (node (ref "C5") (pin "1") (pinfunction "1_1") (pintype "passive"))
      (node (ref "C6") (pin "1") (pinfunction "1_1") (pintype "passive"))
      (node (ref "C7") (pin "1") (pinfunction "1_1") (pintype "passive"))
      (node (ref "C8") (pin "1") (pinfunction "1_1") (pintype "passive"))
      (node (ref "C9") (pin "1") (pinfunction "1_1") (pintype "passive"))
      (node (ref "CR1") (pin "DC-") (pinfunction "DC-_DC-") (pintype "passive"))
      (node (ref "J1") (pin "10") (pinfunction "GND_10") (pintype "passive"))
      (node (ref "J1") (pin "12") (pinfunction "GND_12") (pintype "passive"))
      (node (ref "J1") (pin "14") (pinfunction "GND_14") (pintype "passive"))
      (node (ref "J1") (pin "16") (pinfunction "GND_16") (pintype "passive"))
      (node (ref "J1") (pin "18") (pinfunction "GND_18") (pintype "passive"))
      (node (ref "J1") (pin "20") (pinfunction "GND_20") (pintype "passive"))
      (node (ref "J1") (pin "4") (pinfunction "GND_4") (pintype "passive"))
      (node (ref "J1") (pin "6") (pinfunction "GND_6") (pintype "passive"))
      (node (ref "J1") (pin "8") (pinfunction "GND_8") (pintype "passive"))
      (node (ref "JP1") (pin "5") (pinfunction "5_5") (pintype "passive"))
      (node (ref "JP1") (pin "6") (pinfunction "6_6") (pintype "passive"))
      (node (ref "R12") (pin "1") (pinfunction "1_1") (pintype "passive"))
      (node (ref "R3") (pin "2") (pinfunction "2_2") (pintype "passive"))
      (node (ref "U1") (pin "107") (pinfunction "VSS_107") (pintype "passive"))
      (node (ref "U1") (pin "120") (pinfunction "VSS_120") (pintype "passive"))
      (node (ref "U1") (pin "130") (pinfunction "VSS_130") (pintype "passive"))
      (node (ref "U1") (pin "16") (pinfunction "VSS_16") (pintype "passive"))
      (node (ref "U1") (pin "31") (pinfunction "VSSA_31") (pintype "passive"))
      (node (ref "U1") (pin "38") (pinfunction "VSS_38") (pintype "passive"))
      (node (ref "U1") (pin "51") (pinfunction "VSS_51") (pintype "passive"))
      (node (ref "U1") (pin "61") (pinfunction "VSS_61") (pintype "passive"))
      (node (ref "U1") (pin "83") (pinfunction "VSS_83") (pintype "passive"))
      (node (ref "U1") (pin "94") (pinfunction "VSS_94") (pintype "passive"))
    )
    (net (code "117") (name "Net-(JP1-Pad3)") (class "Default")
      (node (ref "JP1") (pin "3") (pinfunction "3_3") (pintype "passive"))
      (node (ref "R9") (pin "2") (pinfunction "2_2") (pintype "passive"))
    )
    (net (code "118") (name "Net-(JP1-Pad4)") (class "Default")
      (node (ref "JP1") (pin "4") (pinfunction "4_4") (pintype "passive"))
      (node (ref "R10") (pin "1") (pinfunction "1_1") (pintype "passive"))
    )
    (net (code "119") (name "Net-(U1-PC14-OSC32_IN)") (class "Default")
      (node (ref "C1") (pin "2") (pinfunction "2_2") (pintype "passive"))
      (node (ref "U1") (pin "8") (pinfunction "PC14-OSC32_IN_8") (pintype "passive"))
      (node (ref "X1") (pin "2") (pinfunction "2_2") (pintype "passive"))
    )
    (net (code "120") (name "Net-(U1-PC15-OSC32_OUT)") (class "Default")
      (node (ref "C2") (pin "2") (pinfunction "2_2") (pintype "passive"))
      (node (ref "U1") (pin "9") (pinfunction "PC15-OSC32_OUT_9") (pintype "passive"))
      (node (ref "X1") (pin "1") (pinfunction "1_1") (pintype "passive"))
    )
    (net (code "121") (name "Net-(U1-PDR_ON)") (class "Default")
      (node (ref "R3") (pin "1") (pinfunction "1_1") (pintype "passive"))
      (node (ref "R4") (pin "1") (pinfunction "1_1") (pintype "passive"))
      (node (ref "U1") (pin "143") (pinfunction "PDR_ON_143") (pintype "passive"))
    )
    (net (code "122") (name "Net-(U1-PH0-OSC_IN)") (class "Default")
      (node (ref "C3") (pin "2") (pinfunction "2_2") (pintype "passive"))
      (node (ref "R1") (pin "2") (pinfunction "2_2") (pintype "passive"))
      (node (ref "U1") (pin "23") (pinfunction "PH0-OSC_IN_23") (pintype "passive"))
      (node (ref "X2") (pin "1") (pinfunction "1_1") (pintype "passive"))
    )
    (net (code "123") (name "Net-(U1-PH1-OSC_OUT)") (class "Default")
      (node (ref "C4") (pin "2") (pinfunction "2_2") (pintype "passive"))
      (node (ref "R1") (pin "1") (pinfunction "1_1") (pintype "passive"))
      (node (ref "U1") (pin "24") (pinfunction "PH1-OSC_OUT_24") (pintype "passive"))
      (node (ref "X2") (pin "2") (pinfunction "2_2") (pintype "passive"))
    )
    (net (code "124") (name "Net-(U1-Vcap_1)") (class "Default")
      (node (ref "C5") (pin "2") (pinfunction "2_2") (pintype "passive"))
      (node (ref "U1") (pin "71") (pinfunction "Vcap_1_71") (pintype "passive"))
    )
    (net (code "125") (name "Net-(U1-Vcap_2)") (class "Default")
      (node (ref "C6") (pin "2") (pinfunction "2_2") (pintype "passive"))
      (node (ref "U1") (pin "106") (pinfunction "Vcap_2_106") (pintype "passive"))
    )
    (net (code "126") (name "Net-(VD2-A)") (class "Default")
      (node (ref "CR1") (pin "DC+") (pinfunction "DC+_DC+") (pintype "passive"))
      (node (ref "VD2") (pin "1") (pinfunction "A_1") (pintype "passive"))
    )
    (net (code "127") (name "unconnected-(J1-NC-Pad11)") (class "Default")
      (node (ref "J1") (pin "11") (pinfunction "NC_11") (pintype "passive+no_connect"))
    )
    (net (code "128") (name "unconnected-(J1-NC-Pad17)") (class "Default")
      (node (ref "J1") (pin "17") (pinfunction "NC_17") (pintype "passive+no_connect"))
    )
    (net (code "129") (name "unconnected-(J1-NC-Pad19)") (class "Default")
      (node (ref "J1") (pin "19") (pinfunction "NC_19") (pintype "passive+no_connect"))
    )
  )
)
